# circuit_1layer.net
KiCad netlist of a schematic drawn in EAGLE
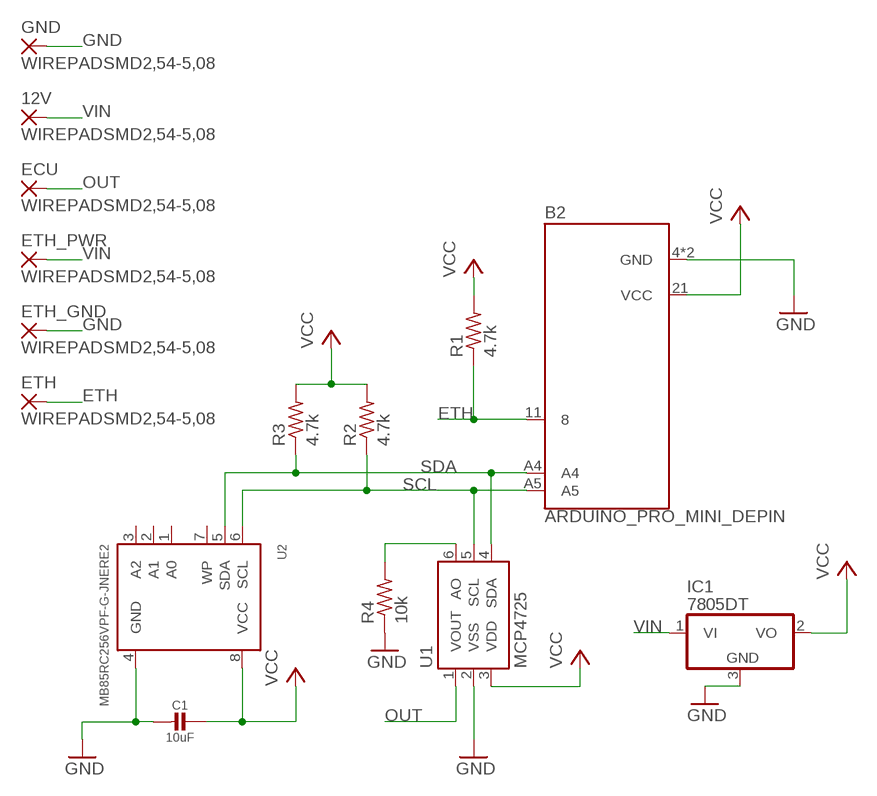
[diagram p0: schematic, sheet 1]

(export (version "E")
  (design (tool "Eeschema 10.0.6"))
  (components
    (comp (ref "12V")
      (value "WIREPADSMD2,54-5,08")
      (footprint "eagle-import:SMD2,54-5,08")
      (libsource (lib "eagle-import") (part "WIREPADSMD2,54-5,08"))
    )
    (comp (ref "B2")
      (value "ARDUINO_PRO_MINI_DEPIN")
      (footprint "eagle-import:ARDUINO_PRO_MINI")
      (libsource (lib "eagle-import") (part "ARDUINO_PRO_MINI_DEPIN"))
    )
    (comp (ref "C1")
      (value "10uF")
      (footprint "eagle-import:_0805MP")
      (libsource (lib "eagle-import") (part "CAP_CERAMIC_0805MP"))
    )
    (comp (ref "ECU")
      (value "WIREPADSMD2,54-5,08")
      (footprint "eagle-import:SMD2,54-5,08")
      (libsource (lib "eagle-import") (part "WIREPADSMD2,54-5,08"))
    )
    (comp (ref "ETH")
      (value "WIREPADSMD2,54-5,08")
      (footprint "eagle-import:SMD2,54-5,08")
      (libsource (lib "eagle-import") (part "WIREPADSMD2,54-5,08"))
    )
    (comp (ref "ETH_GND")
      (value "WIREPADSMD2,54-5,08")
      (footprint "eagle-import:SMD2,54-5,08")
      (libsource (lib "eagle-import") (part "WIREPADSMD2,54-5,08"))
    )
    (comp (ref "ETH_PWR")
      (value "WIREPADSMD2,54-5,08")
      (footprint "eagle-import:SMD2,54-5,08")
      (libsource (lib "eagle-import") (part "WIREPADSMD2,54-5,08"))
    )
    (comp (ref "GND")
      (value "WIREPADSMD2,54-5,08")
      (footprint "eagle-import:SMD2,54-5,08")
      (libsource (lib "eagle-import") (part "WIREPADSMD2,54-5,08"))
    )
    (comp (ref "IC1")
      (value "7805DT")
      (footprint "eagle-import:TO252")
      (libsource (lib "eagle-import") (part "78DT05"))
    )
    (comp (ref "R1")
      (value "4.7k")
      (footprint "eagle-import:R0603")
      (libsource (lib "eagle-import") (part "R-US_R0603"))
    )
    (comp (ref "R2")
      (value "4.7k")
      (footprint "eagle-import:R0603")
      (libsource (lib "eagle-import") (part "R-US_R0603"))
    )
    (comp (ref "R3")
      (value "4.7k")
      (footprint "eagle-import:R0603")
      (libsource (lib "eagle-import") (part "R-US_R0603"))
    )
    (comp (ref "R4")
      (value "10k")
      (footprint "eagle-import:R0603")
      (libsource (lib "eagle-import") (part "R-US_R0603"))
    )
    (comp (ref "U1")
      (value "MCP4725")
      (footprint "eagle-import:SOT23-6")
      (libsource (lib "eagle-import") (part "MCP4725SOT-23"))
    )
    (comp (ref "U2")
      (value "MB85RC256VPF-G-JNERE2")
      (footprint "eagle-import:SOIC8_208MIL")
      (libsource (lib "eagle-import") (part "FRAM_SOIC8_I2C"))
    )
  )
  (nets
    (net (code "1") (name "/ETH") (class "Default")
      (node (ref "B2") (pin "11") (pinfunction "8_11") (pintype "bidirectional"))
      (node (ref "ETH") (pin "1") (pinfunction "P_1") (pintype "passive"))
      (node (ref "R1") (pin "1") (pinfunction "1_1") (pintype "passive"))
    )
    (net (code "2") (name "/OUT") (class "Default")
      (node (ref "ECU") (pin "1") (pinfunction "P_1") (pintype "passive"))
      (node (ref "U1") (pin "1") (pinfunction "VOUT_1") (pintype "bidirectional"))
    )
    (net (code "3") (name "/SCL") (class "Default")
      (node (ref "B2") (pin "A5") (pinfunction "A5_A5") (pintype "bidirectional"))
      (node (ref "R2") (pin "1") (pinfunction "1_1") (pintype "passive"))
      (node (ref "U1") (pin "5") (pinfunction "SCL_5") (pintype "bidirectional"))
      (node (ref "U2") (pin "6") (pinfunction "SCL_6") (pintype "input"))
    )
    (net (code "4") (name "/SDA") (class "Default")
      (node (ref "B2") (pin "A4") (pinfunction "A4_A4") (pintype "bidirectional"))
      (node (ref "R3") (pin "1") (pinfunction "1_1") (pintype "passive"))
      (node (ref "U1") (pin "4") (pinfunction "SDA_4") (pintype "bidirectional"))
      (node (ref "U2") (pin "5") (pinfunction "SDA_5") (pintype "bidirectional"))
    )
    (net (code "5") (name "/VIN") (class "Default")
      (node (ref "12V") (pin "1") (pinfunction "P_1") (pintype "passive"))
      (node (ref "ETH_PWR") (pin "1") (pinfunction "P_1") (pintype "passive"))
      (node (ref "IC1") (pin "1") (pinfunction "VI_1") (pintype "input"))
    )
    (net (code "6") (name "GND") (class "Default")
      (node (ref "B2") (pin "23") (pinfunction "GND_23") (pintype "power_in"))
      (node (ref "B2") (pin "4") (pinfunction "GND_4") (pintype "power_in"))
      (node (ref "C1") (pin "2") (pinfunction "2_2") (pintype "passive"))
      (node (ref "ETH_GND") (pin "1") (pinfunction "P_1") (pintype "passive"))
      (node (ref "GND") (pin "1") (pinfunction "P_1") (pintype "passive"))
      (node (ref "IC1") (pin "3") (pinfunction "GND_3") (pintype "passive"))
      (node (ref "R4") (pin "1") (pinfunction "1_1") (pintype "passive"))
      (node (ref "U1") (pin "2") (pinfunction "VSS_2") (pintype "bidirectional"))
      (node (ref "U2") (pin "4") (pinfunction "GND_4") (pintype "power_in"))
    )
    (net (code "7") (name "Net-(U1-AO)") (class "Default")
      (node (ref "R4") (pin "2") (pinfunction "2_2") (pintype "passive"))
      (node (ref "U1") (pin "6") (pinfunction "AO_6") (pintype "bidirectional"))
    )
    (net (code "8") (name "VCC") (class "Default")
      (node (ref "B2") (pin "21") (pinfunction "VCC_21") (pintype "power_in"))
      (node (ref "C1") (pin "1") (pinfunction "1_1") (pintype "passive"))
      (node (ref "IC1") (pin "2") (pinfunction "VO_2") (pintype "passive"))
      (node (ref "R1") (pin "2") (pinfunction "2_2") (pintype "passive"))
      (node (ref "R2") (pin "2") (pinfunction "2_2") (pintype "passive"))
      (node (ref "R3") (pin "2") (pinfunction "2_2") (pintype "passive"))
      (node (ref "U1") (pin "3") (pinfunction "VDD_3") (pintype "bidirectional"))
      (node (ref "U2") (pin "8") (pinfunction "VCC_8") (pintype "power_in"))
    )
    (net (code "9") (name "unconnected-(U2-A0-Pad1)") (class "Default")
      (node (ref "U2") (pin "1") (pinfunction "A0_1") (pintype "input"))
    )
    (net (code "10") (name "unconnected-(U2-A1-Pad2)") (class "Default")
      (node (ref "U2") (pin "2") (pinfunction "A1_2") (pintype "input"))
    )
    (net (code "11") (name "unconnected-(U2-A2-Pad3)") (class "Default")
      (node (ref "U2") (pin "3") (pinfunction "A2_3") (pintype "input"))
    )
    (net (code "12") (name "unconnected-(U2-WP-Pad7)") (class "Default")
      (node (ref "U2") (pin "7") (pinfunction "WP_7") (pintype "input"))
    )
  )
)
